# mag_pos_connect.net
KiCad netlist of a schematic drawn in Altium Designer
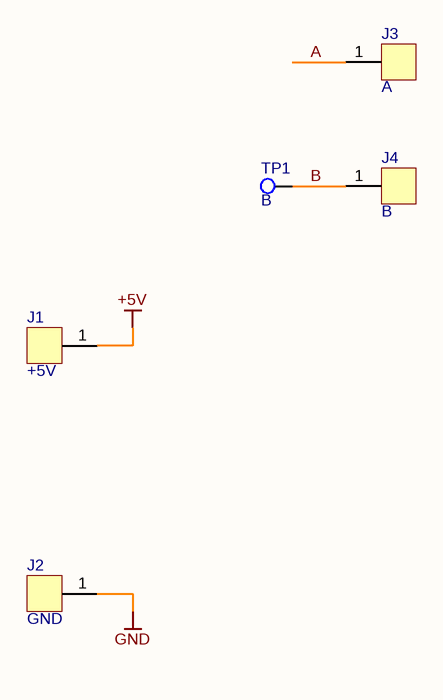
[diagram p0: mag_pos_connect.SchDoc]

(export (version "E")
  (design (tool "Eeschema 10.0.6"))
  (components
    (comp (ref "J1")
      (value "+5V")
      (footprint "mag_pos:WIRE_1MM_1.5MM_THT")
      (description "1mm Wire")
      (libsource (lib "mag_pos") (part "Wire_1MM"))
    )
    (comp (ref "J2")
      (value "GND")
      (footprint "mag_pos:WIRE_1MM_1.5MM_THT")
      (description "1mm Wire")
      (libsource (lib "mag_pos") (part "Wire_1MM"))
    )
    (comp (ref "J3")
      (value "A")
      (footprint "mag_pos:WIRE_1MM_1.5MM_THT")
      (description "1mm Wire")
      (libsource (lib "") (part "Wire_1MM_1"))
    )
    (comp (ref "J4")
      (value "B")
      (footprint "mag_pos:WIRE_1MM_1.5MM_THT")
      (description "1mm Wire")
      (libsource (lib "") (part "Wire_1MM_1"))
    )
    (comp (ref "TP1")
      (value "B")
      (footprint "mag_pos:TP_SMD_1MM")
      (description "Testpoint SMD 1mm")
      (libsource (lib "mag_pos") (part "TP_SMD_1mm"))
    )
  )
  (nets
    (net (code "1") (name "+5V") (class "Default")
      (node (ref "J1") (pin "1") (pinfunction "1_1") (pintype "passive"))
    )
    (net (code "2") (name "/A") (class "Default")
      (node (ref "J3") (pin "1") (pinfunction "1_1") (pintype "passive"))
    )
    (net (code "3") (name "/B") (class "Default")
      (node (ref "J4") (pin "1") (pinfunction "1_1") (pintype "passive"))
      (node (ref "TP1") (pin "1") (pinfunction "1_1") (pintype "passive"))
    )
    (net (code "4") (name "GND") (class "Default")
      (node (ref "J2") (pin "1") (pinfunction "1_1") (pintype "passive"))
    )
  )
)
